# 9_M_2_B_M.net
KiCad netlist of a schematic drawn in Altium Designer
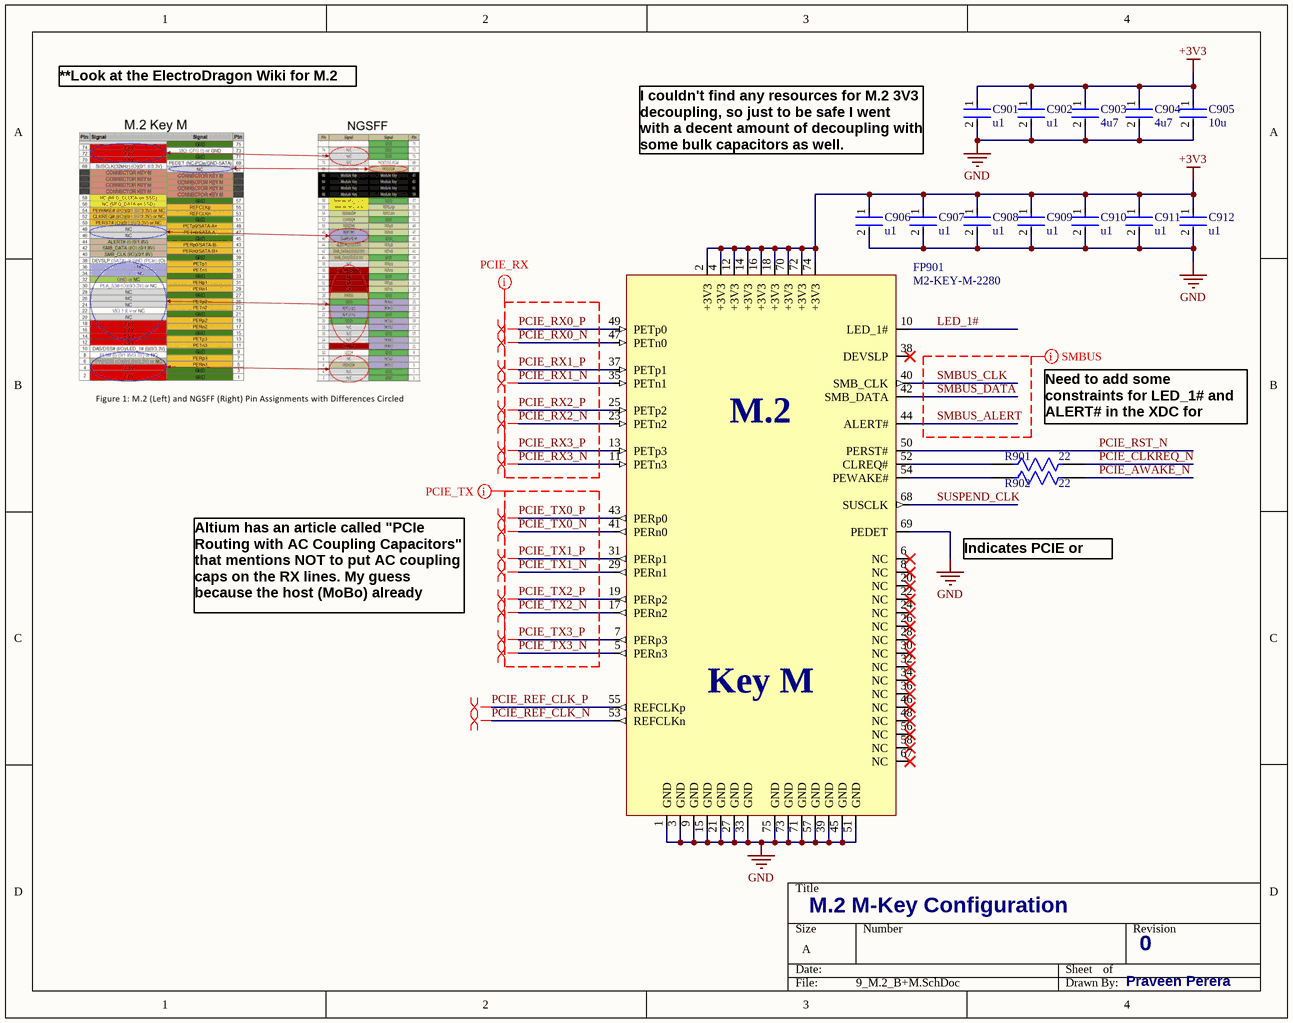
[diagram p0: 9_M.2_B+M.SchDoc]

(export (version "E")
  (design (tool "Eeschema 10.0.6"))
  (components
    (comp (ref "C901")
      (value "u1")
      (footprint "FP-CL891-IPC_C")
      (description "CL05B104KB5NNNC\r\n\r\nCap Ceramic 100nF 50V X7R ±10% SMD 0402 +125°C Paper T/R")
      (libsource (lib "Altium Content Vault") (part "b4654b650e69147ec39a6b967a45e02"))
    )
    (comp (ref "C902")
      (value "u1")
      (footprint "FP-CL891-IPC_C")
      (description "CL05B104KB5NNNC\r\n\r\nCap Ceramic 100nF 50V X7R ±10% SMD 0402 +125°C Paper T/R")
      (libsource (lib "Altium Content Vault") (part "b4654b650e69147ec39a6b967a45e02"))
    )
    (comp (ref "C903")
      (value "4u7")
      (footprint "FP-CL829-IPC_C")
      (description "CL05A475MO5NUNC\r\n\r\nCap Ceramic 4.7uF 16V X5R ±20% SMD 0402 +85°C Paper T/R")
      (fields (field (name "TOLERANCE") "20%"))
      (libsource (lib "Altium Content Vault") (part "b4654b650e69147ec39a6b967a45e02"))
    )
    (comp (ref "C904")
      (value "4u7")
      (footprint "FP-CL829-IPC_C")
      (description "CL05A475MO5NUNC\r\n\r\nCap Ceramic 4.7uF 16V X5R ±20% SMD 0402 +85°C Paper T/R")
      (fields (field (name "TOLERANCE") "20%"))
      (libsource (lib "Altium Content Vault") (part "b4654b650e69147ec39a6b967a45e02"))
    )
    (comp (ref "C905")
      (value "10u")
      (footprint "FP-CL05A106MP5NUNC-MFG")
      (description "CL05A106MP5NUNC\r\n\r\nCAP CER 10UF 10V X5R 0402")
      (fields
        (field (name "OCTOPART") "https://octopart.com/cl05a106mp5nunc-samsung-22457395")
        (field (name "TOLERANCE") "20%")
      )
      (libsource (lib "Altium Content Vault") (part "b4654b650e69147ec39a6b967a45e02"))
    )
    (comp (ref "C906")
      (value "u1")
      (footprint "FP-CL891-IPC_C")
      (description "CL05B104KB5NNNC\r\n\r\nCap Ceramic 100nF 50V X7R ±10% SMD 0402 +125°C Paper T/R")
      (libsource (lib "Altium Content Vault") (part "b4654b650e69147ec39a6b967a45e02"))
    )
    (comp (ref "C907")
      (value "u1")
      (footprint "FP-CL891-IPC_C")
      (description "CL05B104KB5NNNC\r\n\r\nCap Ceramic 100nF 50V X7R ±10% SMD 0402 +125°C Paper T/R")
      (libsource (lib "Altium Content Vault") (part "b4654b650e69147ec39a6b967a45e02"))
    )
    (comp (ref "C908")
      (value "u1")
      (footprint "FP-CL891-IPC_C")
      (description "CL05B104KB5NNNC\r\n\r\nCap Ceramic 100nF 50V X7R ±10% SMD 0402 +125°C Paper T/R")
      (libsource (lib "Altium Content Vault") (part "b4654b650e69147ec39a6b967a45e02"))
    )
    (comp (ref "C909")
      (value "u1")
      (footprint "FP-CL891-IPC_C")
      (description "CL05B104KB5NNNC\r\n\r\nCap Ceramic 100nF 50V X7R ±10% SMD 0402 +125°C Paper T/R")
      (libsource (lib "Altium Content Vault") (part "b4654b650e69147ec39a6b967a45e02"))
    )
    (comp (ref "C910")
      (value "u1")
      (footprint "FP-CL891-IPC_C")
      (description "CL05B104KB5NNNC\r\n\r\nCap Ceramic 100nF 50V X7R ±10% SMD 0402 +125°C Paper T/R")
      (libsource (lib "Altium Content Vault") (part "b4654b650e69147ec39a6b967a45e02"))
    )
    (comp (ref "C911")
      (value "u1")
      (footprint "FP-CL891-IPC_C")
      (description "CL05B104KB5NNNC\r\n\r\nCap Ceramic 100nF 50V X7R ±10% SMD 0402 +125°C Paper T/R")
      (libsource (lib "Altium Content Vault") (part "b4654b650e69147ec39a6b967a45e02"))
    )
    (comp (ref "C912")
      (value "u1")
      (footprint "FP-CL891-IPC_C")
      (description "CL05B104KB5NNNC\r\n\r\nCap Ceramic 100nF 50V X7R ±10% SMD 0402 +125°C Paper T/R")
      (libsource (lib "Altium Content Vault") (part "b4654b650e69147ec39a6b967a45e02"))
    )
    (comp (ref "FP901")
      (value "M2-KEY-M-2280")
      (footprint "M2-KEY-M-2280")
      (description "M.2 Key M 22mm x 80mm")
      (libsource (lib "Withanage Perera") (part "M2-KEY-M-2280"))
    )
    (comp (ref "R901")
      (value "22")
      (footprint "FP-RMCF0201-IPC_C")
      (description "RMCF0201JG22R0\r\n\r\n22Ω ±5% 0.05W 0201 Thick Film Chip Resistor AEC-Q200 compliant")
      (fields (field (name "TOLERANCE") "5%"))
      (libsource (lib "Altium Content Vault") (part "1029c3af85768c4190bb7ad29bc67b5"))
    )
    (comp (ref "R902")
      (value "22")
      (footprint "FP-RMCF0201-IPC_C")
      (description "RMCF0201JG22R0\r\n\r\n22Ω ±5% 0.05W 0201 Thick Film Chip Resistor AEC-Q200 compliant")
      (fields (field (name "TOLERANCE") "5%"))
      (libsource (lib "Altium Content Vault") (part "1029c3af85768c4190bb7ad29bc67b5"))
    )
  )
  (nets
    (net (code "1") (name "+3V3") (class "Default")
      (node (ref "C901") (pin "1") (pinfunction "1_1") (pintype "passive"))
      (node (ref "C902") (pin "1") (pinfunction "1_1") (pintype "passive"))
      (node (ref "C903") (pin "1") (pinfunction "1_1") (pintype "passive"))
      (node (ref "C904") (pin "1") (pinfunction "1_1") (pintype "passive"))
      (node (ref "C905") (pin "1") (pinfunction "1_1") (pintype "passive"))
      (node (ref "C906") (pin "1") (pinfunction "1_1") (pintype "passive"))
      (node (ref "C907") (pin "1") (pinfunction "1_1") (pintype "passive"))
      (node (ref "C908") (pin "1") (pinfunction "1_1") (pintype "passive"))
      (node (ref "C909") (pin "1") (pinfunction "1_1") (pintype "passive"))
      (node (ref "C910") (pin "1") (pinfunction "1_1") (pintype "passive"))
      (node (ref "C911") (pin "1") (pinfunction "1_1") (pintype "passive"))
      (node (ref "C912") (pin "1") (pinfunction "1_1") (pintype "passive"))
      (node (ref "FP901") (pin "12") (pinfunction "+3V3_12") (pintype "power_in"))
      (node (ref "FP901") (pin "14") (pinfunction "+3V3_14") (pintype "power_in"))
      (node (ref "FP901") (pin "16") (pinfunction "+3V3_16") (pintype "power_in"))
      (node (ref "FP901") (pin "18") (pinfunction "+3V3_18") (pintype "power_in"))
      (node (ref "FP901") (pin "2") (pinfunction "+3V3_2") (pintype "power_in"))
      (node (ref "FP901") (pin "4") (pinfunction "+3V3_4") (pintype "power_in"))
      (node (ref "FP901") (pin "70") (pinfunction "+3V3_70") (pintype "power_in"))
      (node (ref "FP901") (pin "72") (pinfunction "+3V3_72") (pintype "power_in"))
      (node (ref "FP901") (pin "74") (pinfunction "+3V3_74") (pintype "power_in"))
    )
    (net (code "2") (name "/LED_1#") (class "Default")
      (node (ref "FP901") (pin "10") (pinfunction "LED_1#_10") (pintype "passive"))
    )
    (net (code "3") (name "/PCIE_AWAKE_N") (class "Default")
      (node (ref "R902") (pin "2") (pinfunction "2_2") (pintype "passive"))
    )
    (net (code "4") (name "/PCIE_CLKREQ_N") (class "Default")
      (node (ref "R901") (pin "2") (pinfunction "2_2") (pintype "passive"))
    )
    (net (code "5") (name "/PCIE_REF_CLK_N") (class "Default")
      (node (ref "FP901") (pin "53") (pinfunction "REFCLKn_53") (pintype "output"))
    )
    (net (code "6") (name "/PCIE_REF_CLK_P") (class "Default")
      (node (ref "FP901") (pin "55") (pinfunction "REFCLKp_55") (pintype "output"))
    )
    (net (code "7") (name "/PCIE_RST_N") (class "Default")
      (node (ref "FP901") (pin "50") (pinfunction "PERST#_50") (pintype "passive"))
    )
    (net (code "8") (name "/PCIE_RX0_N") (class "Default")
      (node (ref "FP901") (pin "47") (pinfunction "PETn0_47") (pintype "input"))
    )
    (net (code "9") (name "/PCIE_RX0_P") (class "Default")
      (node (ref "FP901") (pin "49") (pinfunction "PETp0_49") (pintype "input"))
    )
    (net (code "10") (name "/PCIE_RX1_N") (class "Default")
      (node (ref "FP901") (pin "35") (pinfunction "PETn1_35") (pintype "input"))
    )
    (net (code "11") (name "/PCIE_RX1_P") (class "Default")
      (node (ref "FP901") (pin "37") (pinfunction "PETp1_37") (pintype "input"))
    )
    (net (code "12") (name "/PCIE_RX2_N") (class "Default")
      (node (ref "FP901") (pin "23") (pinfunction "PETn2_23") (pintype "input"))
    )
    (net (code "13") (name "/PCIE_RX2_P") (class "Default")
      (node (ref "FP901") (pin "25") (pinfunction "PETp2_25") (pintype "input"))
    )
    (net (code "14") (name "/PCIE_RX3_N") (class "Default")
      (node (ref "FP901") (pin "11") (pinfunction "PETn3_11") (pintype "input"))
    )
    (net (code "15") (name "/PCIE_RX3_P") (class "Default")
      (node (ref "FP901") (pin "13") (pinfunction "PETp3_13") (pintype "input"))
    )
    (net (code "16") (name "/PCIE_TX0_N") (class "Default")
      (node (ref "FP901") (pin "41") (pinfunction "PERn0_41") (pintype "output"))
    )
    (net (code "17") (name "/PCIE_TX0_P") (class "Default")
      (node (ref "FP901") (pin "43") (pinfunction "PERp0_43") (pintype "output"))
    )
    (net (code "18") (name "/PCIE_TX1_N") (class "Default")
      (node (ref "FP901") (pin "29") (pinfunction "PERn1_29") (pintype "output"))
    )
    (net (code "19") (name "/PCIE_TX1_P") (class "Default")
      (node (ref "FP901") (pin "31") (pinfunction "PERp1_31") (pintype "output"))
    )
    (net (code "20") (name "/PCIE_TX2_N") (class "Default")
      (node (ref "FP901") (pin "17") (pinfunction "PERn2_17") (pintype "output"))
    )
    (net (code "21") (name "/PCIE_TX2_P") (class "Default")
      (node (ref "FP901") (pin "19") (pinfunction "PERp2_19") (pintype "output"))
    )
    (net (code "22") (name "/PCIE_TX3_N") (class "Default")
      (node (ref "FP901") (pin "5") (pinfunction "PERn3_5") (pintype "output"))
    )
    (net (code "23") (name "/PCIE_TX3_P") (class "Default")
      (node (ref "FP901") (pin "7") (pinfunction "PERp3_7") (pintype "output"))
    )
    (net (code "24") (name "/SMBUS_ALERT") (class "Default")
      (node (ref "FP901") (pin "44") (pinfunction "ALERT#_44") (pintype "passive"))
    )
    (net (code "25") (name "/SMBUS_CLK") (class "Default")
      (node (ref "FP901") (pin "40") (pinfunction "SMB_CLK_40") (pintype "output"))
    )
    (net (code "26") (name "/SMBUS_DATA") (class "Default")
      (node (ref "FP901") (pin "42") (pinfunction "SMB_DATA_42") (pintype "bidirectional"))
    )
    (net (code "27") (name "/SUSPEND_CLK") (class "Default")
      (node (ref "FP901") (pin "68") (pinfunction "SUSCLK_68") (pintype "output"))
    )
    (net (code "28") (name "GND") (class "Default")
      (node (ref "C901") (pin "2") (pinfunction "2_2") (pintype "passive"))
      (node (ref "C902") (pin "2") (pinfunction "2_2") (pintype "passive"))
      (node (ref "C903") (pin "2") (pinfunction "2_2") (pintype "passive"))
      (node (ref "C904") (pin "2") (pinfunction "2_2") (pintype "passive"))
      (node (ref "C905") (pin "2") (pinfunction "2_2") (pintype "passive"))
      (node (ref "C906") (pin "2") (pinfunction "2_2") (pintype "passive"))
      (node (ref "C907") (pin "2") (pinfunction "2_2") (pintype "passive"))
      (node (ref "C908") (pin "2") (pinfunction "2_2") (pintype "passive"))
      (node (ref "C909") (pin "2") (pinfunction "2_2") (pintype "passive"))
      (node (ref "C910") (pin "2") (pinfunction "2_2") (pintype "passive"))
      (node (ref "C911") (pin "2") (pinfunction "2_2") (pintype "passive"))
      (node (ref "C912") (pin "2") (pinfunction "2_2") (pintype "passive"))
      (node (ref "FP901") (pin "1") (pinfunction "GND_1") (pintype "power_in"))
      (node (ref "FP901") (pin "15") (pinfunction "GND_15") (pintype "power_in"))
      (node (ref "FP901") (pin "21") (pinfunction "GND_21") (pintype "power_in"))
      (node (ref "FP901") (pin "27") (pinfunction "GND_27") (pintype "power_in"))
      (node (ref "FP901") (pin "3") (pinfunction "GND_3") (pintype "power_in"))
      (node (ref "FP901") (pin "33") (pinfunction "GND_33") (pintype "power_in"))
      (node (ref "FP901") (pin "39") (pinfunction "GND_39") (pintype "power_in"))
      (node (ref "FP901") (pin "45") (pinfunction "GND_45") (pintype "power_in"))
      (node (ref "FP901") (pin "51") (pinfunction "GND_51") (pintype "power_in"))
      (node (ref "FP901") (pin "57") (pinfunction "GND_57") (pintype "power_in"))
      (node (ref "FP901") (pin "69") (pinfunction "PEDET_69") (pintype "passive"))
      (node (ref "FP901") (pin "71") (pinfunction "GND_71") (pintype "power_in"))
      (node (ref "FP901") (pin "73") (pinfunction "GND_73") (pintype "power_in"))
      (node (ref "FP901") (pin "75") (pinfunction "GND_75") (pintype "power_in"))
      (node (ref "FP901") (pin "9") (pinfunction "GND_9") (pintype "power_in"))
    )
    (net (code "29") (name "Net-(FP901-CLREQ#)") (class "Default")
      (node (ref "FP901") (pin "52") (pinfunction "CLREQ#_52") (pintype "passive"))
      (node (ref "R901") (pin "1") (pinfunction "1_1") (pintype "passive"))
    )
    (net (code "30") (name "Net-(FP901-PEWAKE#)") (class "Default")
      (node (ref "FP901") (pin "54") (pinfunction "PEWAKE#_54") (pintype "passive"))
      (node (ref "R902") (pin "1") (pinfunction "1_1") (pintype "passive"))
    )
    (net (code "31") (name "unconnected-(FP901-DEVSLP-Pad38)") (class "Default")
      (node (ref "FP901") (pin "38") (pinfunction "DEVSLP_38") (pintype "passive+no_connect"))
    )
    (net (code "32") (name "unconnected-(FP901-NC-Pad6)") (class "Default")
      (node (ref "FP901") (pin "6") (pinfunction "NC_6") (pintype "passive+no_connect"))
    )
    (net (code "33") (name "unconnected-(FP901-NC-Pad8)") (class "Default")
      (node (ref "FP901") (pin "8") (pinfunction "NC_8") (pintype "passive+no_connect"))
    )
    (net (code "34") (name "unconnected-(FP901-NC-Pad20)") (class "Default")
      (node (ref "FP901") (pin "20") (pinfunction "NC_20") (pintype "passive+no_connect"))
    )
    (net (code "35") (name "unconnected-(FP901-NC-Pad22)") (class "Default")
      (node (ref "FP901") (pin "22") (pinfunction "NC_22") (pintype "passive+no_connect"))
    )
    (net (code "36") (name "unconnected-(FP901-NC-Pad24)") (class "Default")
      (node (ref "FP901") (pin "24") (pinfunction "NC_24") (pintype "passive+no_connect"))
    )
    (net (code "37") (name "unconnected-(FP901-NC-Pad26)") (class "Default")
      (node (ref "FP901") (pin "26") (pinfunction "NC_26") (pintype "passive+no_connect"))
    )
    (net (code "38") (name "unconnected-(FP901-NC-Pad28)") (class "Default")
      (node (ref "FP901") (pin "28") (pinfunction "NC_28") (pintype "passive+no_connect"))
    )
    (net (code "39") (name "unconnected-(FP901-NC-Pad30)") (class "Default")
      (node (ref "FP901") (pin "30") (pinfunction "NC_30") (pintype "passive+no_connect"))
    )
    (net (code "40") (name "unconnected-(FP901-NC-Pad32)") (class "Default")
      (node (ref "FP901") (pin "32") (pinfunction "NC_32") (pintype "passive+no_connect"))
    )
    (net (code "41") (name "unconnected-(FP901-NC-Pad34)") (class "Default")
      (node (ref "FP901") (pin "34") (pinfunction "NC_34") (pintype "passive+no_connect"))
    )
    (net (code "42") (name "unconnected-(FP901-NC-Pad36)") (class "Default")
      (node (ref "FP901") (pin "36") (pinfunction "NC_36") (pintype "passive+no_connect"))
    )
    (net (code "43") (name "unconnected-(FP901-NC-Pad46)") (class "Default")
      (node (ref "FP901") (pin "46") (pinfunction "NC_46") (pintype "passive+no_connect"))
    )
    (net (code "44") (name "unconnected-(FP901-NC-Pad48)") (class "Default")
      (node (ref "FP901") (pin "48") (pinfunction "NC_48") (pintype "passive+no_connect"))
    )
    (net (code "45") (name "unconnected-(FP901-NC-Pad56)") (class "Default")
      (node (ref "FP901") (pin "56") (pinfunction "NC_56") (pintype "passive+no_connect"))
    )
    (net (code "46") (name "unconnected-(FP901-NC-Pad58)") (class "Default")
      (node (ref "FP901") (pin "58") (pinfunction "NC_58") (pintype "passive+no_connect"))
    )
    (net (code "47") (name "unconnected-(FP901-NC-Pad67)") (class "Default")
      (node (ref "FP901") (pin "67") (pinfunction "NC_67") (pintype "passive+no_connect"))
    )
  )
)
